# kraft.net
KiCad netlist of a schematic drawn in EAGLE
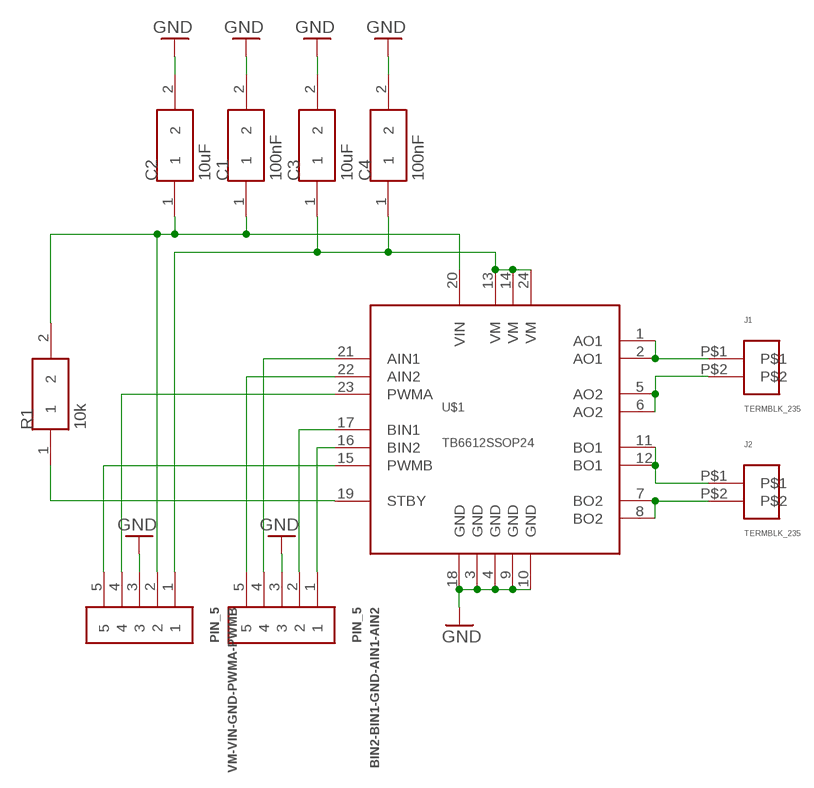
[diagram p0: schematic, sheet 1]

(export (version "E")
  (design (tool "Eeschema 10.0.6"))
  (components
    (comp (ref "BIN2-BIN1-GND-AIN1-AIN2")
      (value "PIN_5")
      (footprint "eagle-import:PIN_5")
      (libsource (lib "eagle-import") (part "PIN_5"))
    )
    (comp (ref "C1")
      (value "100nF")
      (footprint "eagle-import:0805")
      (libsource (lib "eagle-import") (part "CAP0805"))
    )
    (comp (ref "C2")
      (value "10uF")
      (footprint "eagle-import:0805")
      (libsource (lib "eagle-import") (part "CAP0805"))
    )
    (comp (ref "C3")
      (value "10uF")
      (footprint "eagle-import:0805")
      (libsource (lib "eagle-import") (part "CAP0805"))
    )
    (comp (ref "C4")
      (value "100nF")
      (footprint "eagle-import:0805")
      (libsource (lib "eagle-import") (part "CAP0805"))
    )
    (comp (ref "J1")
      (value "TERMBLK_235")
      (footprint "eagle-import:TERMBLK_35_2")
      (libsource (lib "eagle-import") (part "TERMBLK_235"))
    )
    (comp (ref "J2")
      (value "TERMBLK_235")
      (footprint "eagle-import:TERMBLK_35_2")
      (libsource (lib "eagle-import") (part "TERMBLK_235"))
    )
    (comp (ref "R1")
      (value "10k")
      (footprint "eagle-import:0805")
      (libsource (lib "eagle-import") (part "RES0805"))
    )
    (comp (ref "U$1")
      (value "TB6612SSOP24")
      (footprint "eagle-import:SSOP24")
      (libsource (lib "eagle-import") (part "TB6612SSOP24"))
    )
    (comp (ref "VM-VIN-GND-PWMA-PWMB")
      (value "PIN_5")
      (footprint "eagle-import:PIN_5")
      (libsource (lib "eagle-import") (part "PIN_5"))
    )
  )
  (nets
    (net (code "1") (name "GND") (class "Default")
      (node (ref "BIN2-BIN1-GND-AIN1-AIN2") (pin "3") (pinfunction "3_3") (pintype "bidirectional"))
      (node (ref "C1") (pin "2") (pinfunction "2_2") (pintype "bidirectional"))
      (node (ref "C2") (pin "2") (pinfunction "2_2") (pintype "bidirectional"))
      (node (ref "C3") (pin "2") (pinfunction "2_2") (pintype "bidirectional"))
      (node (ref "C4") (pin "2") (pinfunction "2_2") (pintype "bidirectional"))
      (node (ref "U$1") (pin "10") (pinfunction "GND_10") (pintype "bidirectional"))
      (node (ref "U$1") (pin "18") (pinfunction "GND_18") (pintype "bidirectional"))
      (node (ref "U$1") (pin "3") (pinfunction "GND_3") (pintype "bidirectional"))
      (node (ref "U$1") (pin "4") (pinfunction "GND_4") (pintype "bidirectional"))
      (node (ref "U$1") (pin "9") (pinfunction "GND_9") (pintype "bidirectional"))
      (node (ref "VM-VIN-GND-PWMA-PWMB") (pin "3") (pinfunction "3_3") (pintype "bidirectional"))
    )
    (net (code "2") (name "Net-(C3-Pad1)") (class "Default")
      (node (ref "C3") (pin "1") (pinfunction "1_1") (pintype "bidirectional"))
      (node (ref "C4") (pin "1") (pinfunction "1_1") (pintype "bidirectional"))
      (node (ref "U$1") (pin "13") (pinfunction "VM_13") (pintype "bidirectional"))
      (node (ref "U$1") (pin "14") (pinfunction "VM_14") (pintype "bidirectional"))
      (node (ref "U$1") (pin "24") (pinfunction "VM_24") (pintype "bidirectional"))
      (node (ref "VM-VIN-GND-PWMA-PWMB") (pin "1") (pinfunction "1_1") (pintype "bidirectional"))
    )
    (net (code "3") (name "Net-(J1-PadP$1)") (class "Default")
      (node (ref "J1") (pin "P$1") (pinfunction "P$1_P$1") (pintype "bidirectional"))
      (node (ref "U$1") (pin "1") (pinfunction "AO1_1") (pintype "bidirectional"))
      (node (ref "U$1") (pin "2") (pinfunction "AO1_2") (pintype "bidirectional"))
    )
    (net (code "4") (name "Net-(J1-PadP$2)") (class "Default")
      (node (ref "J1") (pin "P$2") (pinfunction "P$2_P$2") (pintype "bidirectional"))
      (node (ref "U$1") (pin "5") (pinfunction "AO2_5") (pintype "bidirectional"))
      (node (ref "U$1") (pin "6") (pinfunction "AO2_6") (pintype "bidirectional"))
    )
    (net (code "5") (name "Net-(J2-PadP$1)") (class "Default")
      (node (ref "J2") (pin "P$1") (pinfunction "P$1_P$1") (pintype "bidirectional"))
      (node (ref "U$1") (pin "11") (pinfunction "BO1_11") (pintype "bidirectional"))
      (node (ref "U$1") (pin "12") (pinfunction "BO1_12") (pintype "bidirectional"))
    )
    (net (code "6") (name "Net-(J2-PadP$2)") (class "Default")
      (node (ref "J2") (pin "P$2") (pinfunction "P$2_P$2") (pintype "bidirectional"))
      (node (ref "U$1") (pin "7") (pinfunction "BO2_7") (pintype "bidirectional"))
      (node (ref "U$1") (pin "8") (pinfunction "BO2_8") (pintype "bidirectional"))
    )
    (net (code "7") (name "Net-(U$1-AIN1)") (class "Default")
      (node (ref "BIN2-BIN1-GND-AIN1-AIN2") (pin "4") (pinfunction "4_4") (pintype "bidirectional"))
      (node (ref "U$1") (pin "21") (pinfunction "AIN1_21") (pintype "bidirectional"))
    )
    (net (code "8") (name "Net-(U$1-AIN2)") (class "Default")
      (node (ref "BIN2-BIN1-GND-AIN1-AIN2") (pin "5") (pinfunction "5_5") (pintype "bidirectional"))
      (node (ref "U$1") (pin "22") (pinfunction "AIN2_22") (pintype "bidirectional"))
    )
    (net (code "9") (name "Net-(U$1-BIN1)") (class "Default")
      (node (ref "BIN2-BIN1-GND-AIN1-AIN2") (pin "2") (pinfunction "2_2") (pintype "bidirectional"))
      (node (ref "U$1") (pin "17") (pinfunction "BIN1_17") (pintype "bidirectional"))
    )
    (net (code "10") (name "Net-(U$1-BIN2)") (class "Default")
      (node (ref "BIN2-BIN1-GND-AIN1-AIN2") (pin "1") (pinfunction "1_1") (pintype "bidirectional"))
      (node (ref "U$1") (pin "16") (pinfunction "BIN2_16") (pintype "bidirectional"))
    )
    (net (code "11") (name "Net-(U$1-PWMA)") (class "Default")
      (node (ref "U$1") (pin "23") (pinfunction "PWMA_23") (pintype "bidirectional"))
      (node (ref "VM-VIN-GND-PWMA-PWMB") (pin "4") (pinfunction "4_4") (pintype "bidirectional"))
    )
    (net (code "12") (name "Net-(U$1-PWMB)") (class "Default")
      (node (ref "U$1") (pin "15") (pinfunction "PWMB_15") (pintype "bidirectional"))
      (node (ref "VM-VIN-GND-PWMA-PWMB") (pin "5") (pinfunction "5_5") (pintype "bidirectional"))
    )
    (net (code "13") (name "Net-(U$1-STBY)") (class "Default")
      (node (ref "R1") (pin "1") (pinfunction "1_1") (pintype "bidirectional"))
      (node (ref "U$1") (pin "19") (pinfunction "STBY_19") (pintype "bidirectional"))
    )
    (net (code "14") (name "Net-(U$1-VIN)") (class "Default")
      (node (ref "C1") (pin "1") (pinfunction "1_1") (pintype "bidirectional"))
      (node (ref "C2") (pin "1") (pinfunction "1_1") (pintype "bidirectional"))
      (node (ref "R1") (pin "2") (pinfunction "2_2") (pintype "bidirectional"))
      (node (ref "U$1") (pin "20") (pinfunction "VIN_20") (pintype "bidirectional"))
      (node (ref "VM-VIN-GND-PWMA-PWMB") (pin "2") (pinfunction "2_2") (pintype "bidirectional"))
    )
  )
)
